# SENSORS.net
KiCad netlist of a schematic drawn in Altium Designer
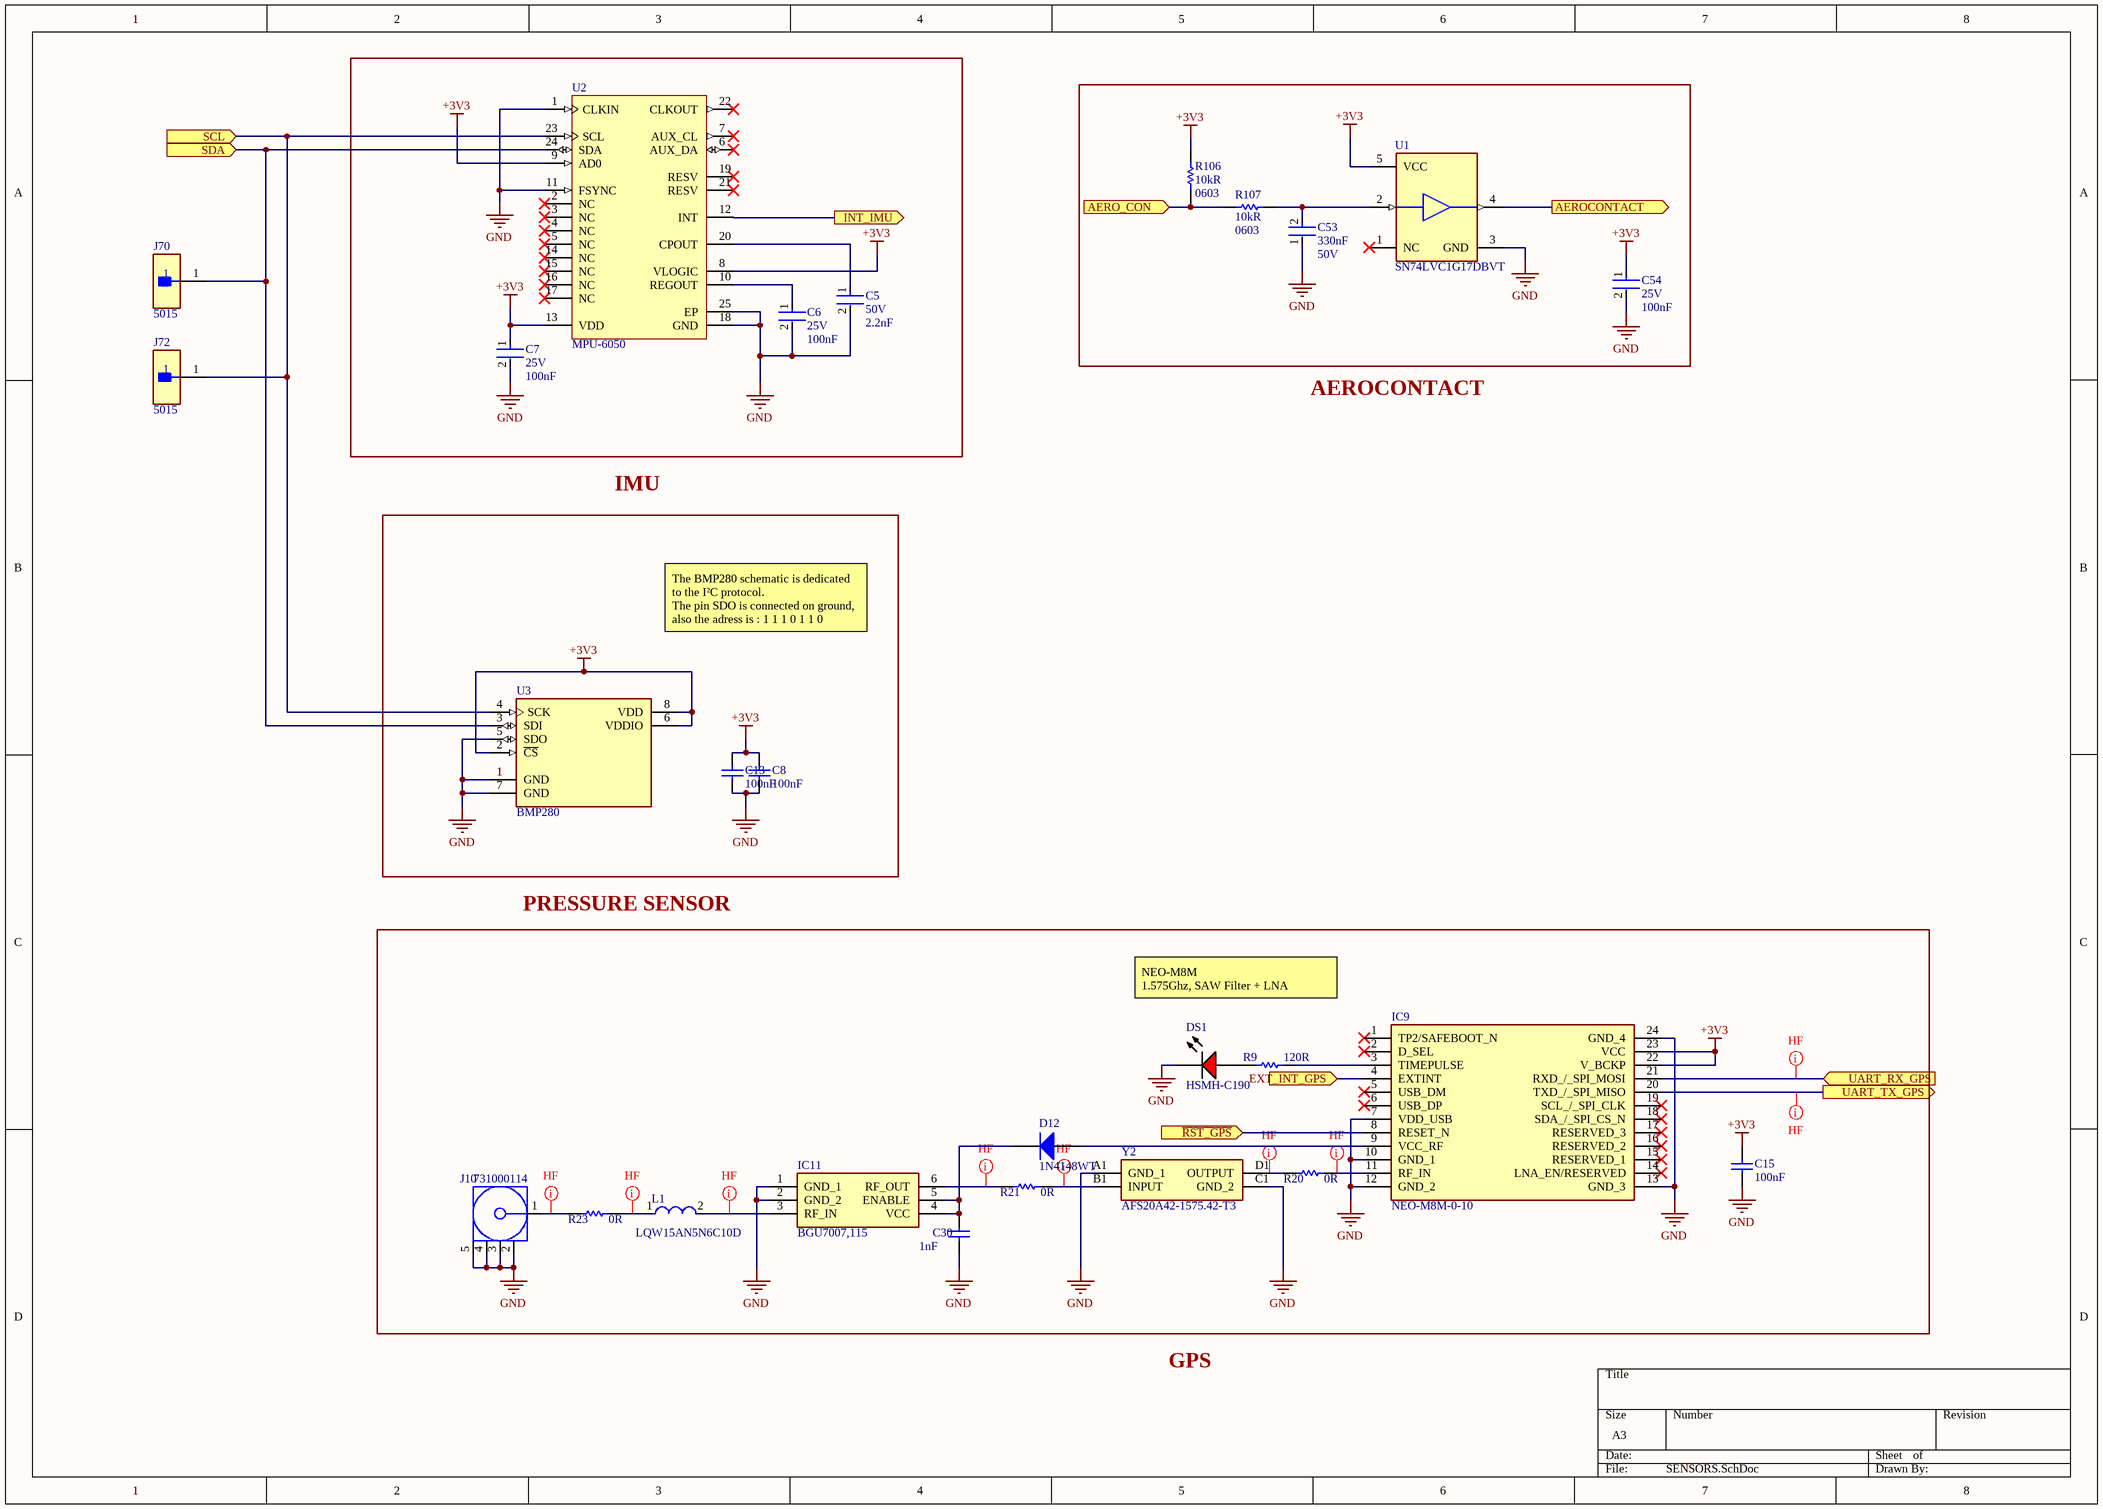
[diagram p0: SENSORS.SchDoc]

(export (version "E")
  (design (tool "Eeschema 10.0.6"))
  (components
    (comp (ref "C5")
      (value "GRM1885C1H222JA01D")
      (footprint "FP-GRM188-0_1-e0_2_0_5-MFG")
      (description "Chip Multilayer Ceramic Capacitors for General Purpose, 0603, 2200pF, C0G, 30ppm/°C, 5%, 50V")
      (fields
        (field (name "VOLTAGE") "50V")
        (field (name "TOLERANCE") "5%")
        (field (name "CAPACITANCE") "2.2nF")
        (field (name "MANUFACTURER") "Murata")
      )
      (libsource (lib "Altium Content Vault") (part "11868f565c42a9108669ba33697ecf6"))
    )
    (comp (ref "C6")
      (value "CGA3E2X7R1E104K080AA")
      (footprint "FP-CGA3E-0_3-0_1-MFG")
      (description "Cap Ceramic 100nF 25V X7R 10% Pad SMD 0603 +125°C Automotive T/R")
      (fields
        (field (name "VOLTAGE RATING (DC)") "25V")
        (field (name "CAPACITANCE") "100nF")
        (field (name "TOLERANCE") "10%")
        (field (name "MANUFACTURER") "TDK")
      )
      (libsource (lib "Altium Content Vault") (part "b4654b650e69147ec39a6b967a45e02"))
    )
    (comp (ref "C7")
      (value "CGA3E2X7R1E104K080AA")
      (footprint "FP-CGA3E-0_3-0_1-MFG")
      (description "Cap Ceramic 100nF 25V X7R 10% Pad SMD 0603 +125°C Automotive T/R")
      (fields
        (field (name "VOLTAGE RATING (DC)") "25V")
        (field (name "CAPACITANCE") "100nF")
        (field (name "TOLERANCE") "10%")
        (field (name "MANUFACTURER") "TDK")
      )
      (libsource (lib "Altium Content Vault") (part "b4654b650e69147ec39a6b967a45e02"))
    )
    (comp (ref "C8")
      (value "100nF")
      (footprint "SAMS-C0603-2_M")
      (description "Multi-layer Ceramic Capacitor, -55 to 125 degC, 2-Pin SMD (0603), RoHS, Tape and Reel")
      (fields (field (name "MANUFACTURER") "Samsung Electro-Mechanics"))
      (libsource (lib "Altium Content Vault") (part "CAP-NP-2"))
    )
    (comp (ref "C13")
      (value "100nF")
      (footprint "SAMS-C0603-2_M")
      (description "Multi-layer Ceramic Capacitor, -55 to 125 degC, 2-Pin SMD (0603), RoHS, Tape and Reel")
      (fields (field (name "MANUFACTURER") "Samsung Electro-Mechanics"))
      (libsource (lib "Altium Content Vault") (part "CAP-NP-2"))
    )
    (comp (ref "C15")
      (value "100nF")
      (footprint "SAMS-C0603-2_M")
      (description "Multi-layer Ceramic Capacitor, -55 to 125 degC, 2-Pin SMD (0603), RoHS, Tape and Reel")
      (fields (field (name "MANUFACTURER") "Samsung Electro-Mechanics"))
      (libsource (lib "Altium Content Vault") (part "CAP-NP-2"))
    )
    (comp (ref "C30")
      (value "1nF")
      (footprint "SAMS-C0603-2_M")
      (description "Multi-layer Ceramic Capacitor, -55 to 125 degC, 2-Pin SMD (0603), RoHS, Tape and Reel")
      (fields (field (name "MANUFACTURER") "Samsung Electro-Mechanics"))
      (libsource (lib "Altium Content Vault") (part "CAP-NP-2"))
    )
    (comp (ref "C53")
      (value "C1608X7R1H334K080AC")
      (footprint "FP-C1608-080-0_1-IPC_B")
      (description "Multilayer Ceramic Capacitors 330nF ±10% 50V X7R SMD 0603")
      (fields
        (field (name "CAPACITANCE") "330nF")
        (field (name "VOLTAGE RATING") "50V")
        (field (name "TOLERANCE") "10%")
        (field (name "VOLTAGE") "50V")
      )
      (libsource (lib "Altium Content Vault") (part "236180d848d6139a670b325ea6854c9"))
    )
    (comp (ref "C54")
      (value "CGA3E2X7R1E104K080AA")
      (footprint "FP-CGA3E-0_3-0_1-MFG")
      (description "Cap Ceramic 100nF 25V X7R 10% Pad SMD 0603 +125°C Automotive T/R")
      (fields
        (field (name "VOLTAGE RATING (DC)") "25V")
        (field (name "CAPACITANCE") "100nF")
        (field (name "TOLERANCE") "10%")
        (field (name "MANUFACTURER") "TDK")
      )
      (libsource (lib "Altium Content Vault") (part "b4654b650e69147ec39a6b967a45e02"))
    )
    (comp (ref "D12")
      (value "1N4148WT")
      (footprint "FAIR-SOD-523F-2_V")
      (description "High Conductance Fast Switching Diode, 75 V, -55 to 150 degC, 2-Pin SOD523F, RoHS")
      (fields (field (name "MANUFACTURER") "Fairchild Semiconductor"))
      (libsource (lib "Altium Content Vault") (part "FAIR-D_K1A2-2"))
    )
    (comp (ref "DS1")
      (value "HSMH-C190")
      (footprint "AVAG-HSMX-C190_V")
      (description "LED Uni-Color Red, 65 mW, 20 mA, -40 to 85 degC, 2-Pin SMD, RoHS, Tape and Reel")
      (libsource (lib "Altium Content Vault") (part "LED-RED-AK-2"))
    )
    (comp (ref "IC9")
      (value "NEO-M8M-0-10")
      (footprint "SamacSys:NEO-M8T")
      (description "Integrated Circuit")
      (libsource (lib "*") (part "NEO-M8M-0-10"))
    )
    (comp (ref "IC11")
      (value "BGU7007,115")
      (footprint "SamacSys:BGU7007115")
      (description "Integrated Circuit")
      (fields (field (name "MOUSER PART NUMBER") "771-BGU7007115"))
      (libsource (lib "*") (part "BGU7007,115"))
    )
    (comp (ref "J10")
      (value "731000114")
      (footprint "MOLX-731000114_V")
      (description "SMA Right-Angle PCB Jack Receptacle, Brass Body, Gold Plated, 50 Ohm, 5-Pin THD, RoHS, Tray")
      (fields (field (name "MANUFACTURER") "Molex"))
      (libsource (lib "Altium Content Vault") (part "CN-S-4F-RF5"))
    )
    (comp (ref "J70")
      (value "5015")
      (footprint "FP-5015-MFG")
      (description "PC TEST POINT MINIATURE")
      (fields
        (field (name "MANUFACTURER") "keystone")
        (field (name "OCTOPART") "https://octopart.com/5015-keystone-3822")
      )
      (libsource (lib "Altium Content Vault") (part "dd45045ce8184df9e99e12baf3f412c"))
    )
    (comp (ref "J72")
      (value "5015")
      (footprint "FP-5015-MFG")
      (description "PC TEST POINT MINIATURE")
      (fields
        (field (name "MANUFACTURER") "keystone")
        (field (name "OCTOPART") "https://octopart.com/5015-keystone-3822")
      )
      (libsource (lib "Altium Content Vault") (part "dd45045ce8184df9e99e12baf3f412c"))
    )
    (comp (ref "L1")
      (value "LQW15AN5N6C10D")
      (footprint "FP-LQW15AN_00-W0_6-0_1-MFG")
      (description "Wire Wound RF Inductor 5.6nH ±0.2nH 800mA 0.051Ω 0402 (1005)")
      (libsource (lib "Altium Content Vault") (part "725321dda6339637d4d059423bc1c3c"))
    )
    (comp (ref "R9")
      (value "120R")
      (footprint "RESC1609X50X30NL8T20")
      (fields (field (name "MANUFACTURER") "Vishay Semiconductor"))
      (libsource (lib "Altium Content Vault") (part "RES-2"))
    )
    (comp (ref "R20")
      (value "0R")
      (footprint "RESC1609X50X30NL8T20")
      (fields (field (name "MANUFACTURER") "Vishay Semiconductor"))
      (libsource (lib "Altium Content Vault") (part "RES-2"))
    )
    (comp (ref "R21")
      (value "0R")
      (footprint "RESC1609X50X30NL8T20")
      (fields (field (name "MANUFACTURER") "Vishay Semiconductor"))
      (libsource (lib "Altium Content Vault") (part "RES-2"))
    )
    (comp (ref "R23")
      (value "0R")
      (footprint "RESC1609X50X30NL8T20")
      (fields (field (name "MANUFACTURER") "Vishay Semiconductor"))
      (libsource (lib "Altium Content Vault") (part "RES-2"))
    )
    (comp (ref "R106")
      (value "ERJ3EKF1002V")
      (footprint "RESC1609X55X30LL15T15")
      (description "Chip Resistor, 10 KOhm, +/- 1%, 0.1 W, -55 to 155 degC, 0603 (1608 Metric), RoHS, Tape and Reel")
      (fields
        (field (name "RESISTANCE") "10kR")
        (field (name "CASE CODE (IMPERIAL)") "0603")
        (field (name "TOLERANCE") "1%")
        (field (name "MANUFACTURER") "Panasonic")
      )
      (libsource (lib "Altium Content Vault") (part "RES-2"))
    )
    (comp (ref "R107")
      (value "ERJ3EKF1002V")
      (footprint "RESC1609X55X30LL15T15")
      (description "Chip Resistor, 10 KOhm, +/- 1%, 0.1 W, -55 to 155 degC, 0603 (1608 Metric), RoHS, Tape and Reel")
      (fields
        (field (name "RESISTANCE") "10kR")
        (field (name "CASE CODE (IMPERIAL)") "0603")
        (field (name "TOLERANCE") "1%")
        (field (name "MANUFACTURER") "Panasonic")
      )
      (libsource (lib "Altium Content Vault") (part "RES-2"))
    )
    (comp (ref "U1")
      (value "SN74LVC1G17DBVT")
      (footprint "FP-DBV0005A-MFG")
      (description "IC BUF NON-INVERT 5.5V SOT23-5")
      (fields
        (field (name "MANUFACTURER") "Texas Instruments")
        (field (name "OCTOPART") "https://octopart.com/sn74lvc1g17dbvt-texas+instruments-2326350")
      )
      (libsource (lib "Altium Content Vault") (part "d67d855942c6c6b24b3bb5c51ad1e18"))
    )
    (comp (ref "U2")
      (value "MPU-6050")
      (footprint "IS-QFN-24_V")
      (fields (field (name "MANUFACTURER") "InvenSense"))
      (libsource (lib "Altium Content Vault") (part "IS-MPU-6050-QFN-24"))
    )
    (comp (ref "U3")
      (value "BMP280")
      (footprint "FP-BMP280-MFG")
      (description "SENSOR PRESSURE ABS")
      (libsource (lib "Altium Content Vault") (part "69b1aacbb03d82763a43fac02afba64"))
    )
    (comp (ref "Y2")
      (value "AFS20A42-1575.42-T3")
      (footprint "SamacSys:AFS20A42157542T3")
      (description "Crystal or Oscillator")
      (fields (field (name "MOUSER PART NUMBER") "815-AFS20A42-1575-T3"))
      (libsource (lib "*") (part "AFS20A42-1575.42-T3"))
    )
  )
  (nets
    (net (code "1") (name "+3V3") (class "Default")
      (node (ref "C13") (pin "2") (pinfunction "2_2") (pintype "passive"))
      (node (ref "C15") (pin "2") (pinfunction "2_2") (pintype "passive"))
      (node (ref "C54") (pin "1") (pinfunction "1_1") (pintype "passive"))
      (node (ref "C7") (pin "1") (pinfunction "1_1") (pintype "passive"))
      (node (ref "C8") (pin "2") (pinfunction "2_2") (pintype "passive"))
      (node (ref "IC9") (pin "22") (pinfunction "V_BCKP_22") (pintype "passive"))
      (node (ref "IC9") (pin "23") (pinfunction "VCC_23") (pintype "passive"))
      (node (ref "R106") (pin "2") (pinfunction "2_2") (pintype "passive"))
      (node (ref "U1") (pin "5") (pinfunction "VCC_5") (pintype "power_in"))
      (node (ref "U2") (pin "13") (pinfunction "VDD_13") (pintype "power_in"))
      (node (ref "U2") (pin "8") (pinfunction "VLOGIC_8") (pintype "power_in"))
      (node (ref "U2") (pin "9") (pinfunction "AD0_9") (pintype "input"))
      (node (ref "U3") (pin "2") (pinfunction "~{CS}_2") (pintype "input"))
      (node (ref "U3") (pin "6") (pinfunction "VDDIO_6") (pintype "power_in"))
      (node (ref "U3") (pin "8") (pinfunction "VDD_8") (pintype "power_in"))
    )
    (net (code "2") (name "/AEROCONTACT") (class "Default")
      (node (ref "U1") (pin "4") (pinfunction "Y_4") (pintype "output"))
    )
    (net (code "3") (name "/AERO_CON") (class "Default")
      (node (ref "R106") (pin "1") (pinfunction "1_1") (pintype "passive"))
      (node (ref "R107") (pin "2") (pinfunction "2_2") (pintype "passive"))
    )
    (net (code "4") (name "/EXT_INT_GPS") (class "Default")
      (node (ref "IC9") (pin "4") (pinfunction "EXTINT_4") (pintype "passive"))
    )
    (net (code "5") (name "/INT_IMU") (class "Default")
      (node (ref "U2") (pin "12") (pinfunction "INT_12") (pintype "open_collector"))
    )
    (net (code "6") (name "/RST_GPS") (class "Default")
      (node (ref "IC9") (pin "8") (pinfunction "RESET_N_8") (pintype "passive"))
    )
    (net (code "7") (name "/SCL") (class "Default")
      (node (ref "J72") (pin "1") (pinfunction "1_1") (pintype "passive"))
      (node (ref "U2") (pin "23") (pinfunction "SCL_23") (pintype "input"))
      (node (ref "U3") (pin "4") (pinfunction "SCK_4") (pintype "input"))
    )
    (net (code "8") (name "/SDA") (class "Default")
      (node (ref "J70") (pin "1") (pinfunction "1_1") (pintype "passive"))
      (node (ref "U2") (pin "24") (pinfunction "SDA_24") (pintype "bidirectional"))
      (node (ref "U3") (pin "3") (pinfunction "SDI_3") (pintype "bidirectional"))
    )
    (net (code "9") (name "/UART_RX_GPS") (class "Default")
      (node (ref "IC9") (pin "21") (pinfunction "RXD_/_SPI_MOSI_21") (pintype "passive"))
    )
    (net (code "10") (name "/UART_TX_GPS") (class "Default")
      (node (ref "IC9") (pin "20") (pinfunction "TXD_/_SPI_MISO_20") (pintype "passive"))
    )
    (net (code "11") (name "GND") (class "Default")
      (node (ref "C13") (pin "1") (pinfunction "1_1") (pintype "passive"))
      (node (ref "C15") (pin "1") (pinfunction "1_1") (pintype "passive"))
      (node (ref "C30") (pin "1") (pinfunction "1_1") (pintype "passive"))
      (node (ref "C5") (pin "2") (pinfunction "2_2") (pintype "passive"))
      (node (ref "C53") (pin "1") (pinfunction "1_1") (pintype "passive"))
      (node (ref "C54") (pin "2") (pinfunction "2_2") (pintype "passive"))
      (node (ref "C6") (pin "2") (pinfunction "2_2") (pintype "passive"))
      (node (ref "C7") (pin "2") (pinfunction "2_2") (pintype "passive"))
      (node (ref "C8") (pin "1") (pinfunction "1_1") (pintype "passive"))
      (node (ref "DS1") (pin "2") (pinfunction "K_2") (pintype "passive"))
      (node (ref "IC11") (pin "1") (pinfunction "GND_1_1") (pintype "passive"))
      (node (ref "IC11") (pin "2") (pinfunction "GND_2_2") (pintype "passive"))
      (node (ref "IC9") (pin "10") (pinfunction "GND_1_10") (pintype "passive"))
      (node (ref "IC9") (pin "12") (pinfunction "GND_2_12") (pintype "passive"))
      (node (ref "IC9") (pin "13") (pinfunction "GND_3_13") (pintype "passive"))
      (node (ref "IC9") (pin "24") (pinfunction "GND_4_24") (pintype "passive"))
      (node (ref "IC9") (pin "7") (pinfunction "VDD_USB_7") (pintype "passive"))
      (node (ref "J10") (pin "2") (pinfunction "2_2") (pintype "passive"))
      (node (ref "J10") (pin "3") (pinfunction "3_3") (pintype "passive"))
      (node (ref "J10") (pin "4") (pinfunction "4_4") (pintype "passive"))
      (node (ref "J10") (pin "5") (pinfunction "5_5") (pintype "passive"))
      (node (ref "U1") (pin "3") (pinfunction "GND_3") (pintype "power_in"))
      (node (ref "U2") (pin "1") (pinfunction "CLKIN_1") (pintype "input"))
      (node (ref "U2") (pin "11") (pinfunction "FSYNC_11") (pintype "input"))
      (node (ref "U2") (pin "18") (pinfunction "GND_18") (pintype "power_in"))
      (node (ref "U2") (pin "25") (pinfunction "EP_25") (pintype "power_in"))
      (node (ref "U3") (pin "1") (pinfunction "GND_1") (pintype "power_in"))
      (node (ref "U3") (pin "5") (pinfunction "SDO_5") (pintype "bidirectional"))
      (node (ref "U3") (pin "7") (pinfunction "GND_7") (pintype "power_in"))
      (node (ref "Y2") (pin "A1") (pinfunction "GND_1_A1") (pintype "passive"))
      (node (ref "Y2") (pin "C1") (pinfunction "GND_2_C1") (pintype "passive"))
    )
    (net (code "12") (name "Net-(D12-A)") (class "Default")
      (node (ref "D12") (pin "2") (pinfunction "A_2") (pintype "passive"))
      (node (ref "IC9") (pin "9") (pinfunction "VCC_RF_9") (pintype "passive"))
    )
    (net (code "13") (name "Net-(D12-K)") (class "Default")
      (node (ref "C30") (pin "2") (pinfunction "2_2") (pintype "passive"))
      (node (ref "D12") (pin "1") (pinfunction "K_1") (pintype "passive"))
      (node (ref "IC11") (pin "4") (pinfunction "VCC_4") (pintype "passive"))
      (node (ref "IC11") (pin "5") (pinfunction "ENABLE_5") (pintype "passive"))
    )
    (net (code "14") (name "Net-(DS1-A)") (class "Default")
      (node (ref "DS1") (pin "1") (pinfunction "A_1") (pintype "passive"))
      (node (ref "R9") (pin "1") (pinfunction "1_1") (pintype "passive"))
    )
    (net (code "15") (name "Net-(IC9-RF_IN)") (class "Default")
      (node (ref "IC9") (pin "11") (pinfunction "RF_IN_11") (pintype "passive"))
      (node (ref "R20") (pin "2") (pinfunction "2_2") (pintype "passive"))
    )
    (net (code "16") (name "Net-(IC9-TIMEPULSE)") (class "Default")
      (node (ref "IC9") (pin "3") (pinfunction "TIMEPULSE_3") (pintype "passive"))
      (node (ref "R9") (pin "2") (pinfunction "2_2") (pintype "passive"))
    )
    (net (code "17") (name "Net-(IC11-RF_IN)") (class "Default")
      (node (ref "IC11") (pin "3") (pinfunction "RF_IN_3") (pintype "passive"))
      (node (ref "L1") (pin "2") (pinfunction "2_2") (pintype "passive"))
    )
    (net (code "18") (name "Net-(IC11-RF_OUT)") (class "Default")
      (node (ref "IC11") (pin "6") (pinfunction "RF_OUT_6") (pintype "passive"))
      (node (ref "R21") (pin "1") (pinfunction "1_1") (pintype "passive"))
    )
    (net (code "19") (name "Net-(J10-Pad1)") (class "Default")
      (node (ref "J10") (pin "1") (pinfunction "1_1") (pintype "passive"))
      (node (ref "R23") (pin "1") (pinfunction "1_1") (pintype "passive"))
    )
    (net (code "20") (name "Net-(L1-Pad1)") (class "Default")
      (node (ref "L1") (pin "1") (pinfunction "1_1") (pintype "passive"))
      (node (ref "R23") (pin "2") (pinfunction "2_2") (pintype "passive"))
    )
    (net (code "21") (name "Net-(U1-A)") (class "Default")
      (node (ref "C53") (pin "2") (pinfunction "2_2") (pintype "passive"))
      (node (ref "R107") (pin "1") (pinfunction "1_1") (pintype "passive"))
      (node (ref "U1") (pin "2") (pinfunction "A_2") (pintype "input"))
    )
    (net (code "22") (name "Net-(U2-CPOUT)") (class "Default")
      (node (ref "C5") (pin "1") (pinfunction "1_1") (pintype "passive"))
      (node (ref "U2") (pin "20") (pinfunction "CPOUT_20") (pintype "passive"))
    )
    (net (code "23") (name "Net-(U2-REGOUT)") (class "Default")
      (node (ref "C6") (pin "1") (pinfunction "1_1") (pintype "passive"))
      (node (ref "U2") (pin "10") (pinfunction "REGOUT_10") (pintype "passive"))
    )
    (net (code "24") (name "Net-(Y2-INPUT)") (class "Default")
      (node (ref "R21") (pin "2") (pinfunction "2_2") (pintype "passive"))
      (node (ref "Y2") (pin "B1") (pinfunction "INPUT_B1") (pintype "passive"))
    )
    (net (code "25") (name "Net-(Y2-OUTPUT)") (class "Default")
      (node (ref "R20") (pin "1") (pinfunction "1_1") (pintype "passive"))
      (node (ref "Y2") (pin "D1") (pinfunction "OUTPUT_D1") (pintype "passive"))
    )
    (net (code "26") (name "unconnected-(IC9-D_SEL-Pad2)") (class "Default")
      (node (ref "IC9") (pin "2") (pinfunction "D_SEL_2") (pintype "passive+no_connect"))
    )
    (net (code "27") (name "unconnected-(IC9-LNA_EN{slash}RESERVED-Pad14)") (class "Default")
      (node (ref "IC9") (pin "14") (pinfunction "LNA_EN/RESERVED_14") (pintype "passive+no_connect"))
    )
    (net (code "28") (name "unconnected-(IC9-RESERVED_1-Pad15)") (class "Default")
      (node (ref "IC9") (pin "15") (pinfunction "RESERVED_1_15") (pintype "passive+no_connect"))
    )
    (net (code "29") (name "unconnected-(IC9-RESERVED_2-Pad16)") (class "Default")
      (node (ref "IC9") (pin "16") (pinfunction "RESERVED_2_16") (pintype "passive+no_connect"))
    )
    (net (code "30") (name "unconnected-(IC9-RESERVED_3-Pad17)") (class "Default")
      (node (ref "IC9") (pin "17") (pinfunction "RESERVED_3_17") (pintype "passive+no_connect"))
    )
    (net (code "31") (name "unconnected-(IC9-SCL_{slash}_SPI_CLK-Pad19)") (class "Default")
      (node (ref "IC9") (pin "19") (pinfunction "SCL_/_SPI_CLK_19") (pintype "passive+no_connect"))
    )
    (net (code "32") (name "unconnected-(IC9-SDA_{slash}_SPI_CS_N-Pad18)") (class "Default")
      (node (ref "IC9") (pin "18") (pinfunction "SDA_/_SPI_CS_N_18") (pintype "passive+no_connect"))
    )
    (net (code "33") (name "unconnected-(IC9-TP2{slash}SAFEBOOT_N-Pad1)") (class "Default")
      (node (ref "IC9") (pin "1") (pinfunction "TP2/SAFEBOOT_N_1") (pintype "passive+no_connect"))
    )
    (net (code "34") (name "unconnected-(IC9-USB_DM-Pad5)") (class "Default")
      (node (ref "IC9") (pin "5") (pinfunction "USB_DM_5") (pintype "passive+no_connect"))
    )
    (net (code "35") (name "unconnected-(IC9-USB_DP-Pad6)") (class "Default")
      (node (ref "IC9") (pin "6") (pinfunction "USB_DP_6") (pintype "passive+no_connect"))
    )
    (net (code "36") (name "unconnected-(U1-NC-Pad1)") (class "Default")
      (node (ref "U1") (pin "1") (pinfunction "NC_1") (pintype "passive+no_connect"))
    )
    (net (code "37") (name "unconnected-(U2-AUX_CL-Pad7)") (class "Default")
      (node (ref "U2") (pin "7") (pinfunction "AUX_CL_7") (pintype "output+no_connect"))
    )
    (net (code "38") (name "unconnected-(U2-AUX_DA-Pad6)") (class "Default")
      (node (ref "U2") (pin "6") (pinfunction "AUX_DA_6") (pintype "bidirectional+no_connect"))
    )
    (net (code "39") (name "unconnected-(U2-CLKOUT-Pad22)") (class "Default")
      (node (ref "U2") (pin "22") (pinfunction "CLKOUT_22") (pintype "output+no_connect"))
    )
    (net (code "40") (name "unconnected-(U2-NC-Pad2)") (class "Default")
      (node (ref "U2") (pin "2") (pinfunction "NC_2") (pintype "passive+no_connect"))
    )
    (net (code "41") (name "unconnected-(U2-NC-Pad3)") (class "Default")
      (node (ref "U2") (pin "3") (pinfunction "NC_3") (pintype "passive+no_connect"))
    )
    (net (code "42") (name "unconnected-(U2-NC-Pad4)") (class "Default")
      (node (ref "U2") (pin "4") (pinfunction "NC_4") (pintype "passive+no_connect"))
    )
    (net (code "43") (name "unconnected-(U2-NC-Pad5)") (class "Default")
      (node (ref "U2") (pin "5") (pinfunction "NC_5") (pintype "passive+no_connect"))
    )
    (net (code "44") (name "unconnected-(U2-NC-Pad14)") (class "Default")
      (node (ref "U2") (pin "14") (pinfunction "NC_14") (pintype "passive+no_connect"))
    )
    (net (code "45") (name "unconnected-(U2-NC-Pad15)") (class "Default")
      (node (ref "U2") (pin "15") (pinfunction "NC_15") (pintype "passive+no_connect"))
    )
    (net (code "46") (name "unconnected-(U2-NC-Pad16)") (class "Default")
      (node (ref "U2") (pin "16") (pinfunction "NC_16") (pintype "passive+no_connect"))
    )
    (net (code "47") (name "unconnected-(U2-NC-Pad17)") (class "Default")
      (node (ref "U2") (pin "17") (pinfunction "NC_17") (pintype "passive+no_connect"))
    )
    (net (code "48") (name "unconnected-(U2-RESV-Pad19)") (class "Default")
      (node (ref "U2") (pin "19") (pinfunction "RESV_19") (pintype "passive+no_connect"))
    )
    (net (code "49") (name "unconnected-(U2-RESV-Pad21)") (class "Default")
      (node (ref "U2") (pin "21") (pinfunction "RESV_21") (pintype "passive+no_connect"))
    )
  )
)
